# power.net
KiCad netlist of a schematic drawn in Altium Designer
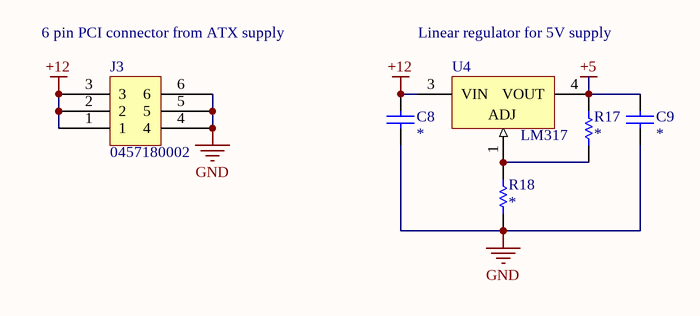
[diagram p0: power.SchDoc]

(export (version "E")
  (design (tool "Eeschema 10.0.6"))
  (components
    (comp (ref "C8")
      (value "*")
      (footprint "C0603")
      (description "0603 Capacitor")
      (fields (field (name "ALTIUM_VALUE") "*"))
      (libsource (lib "PARSEC") (part "C0603"))
    )
    (comp (ref "C9")
      (value "*")
      (footprint "C0805")
      (description "0805 Capacitor")
      (fields (field (name "ALTIUM_VALUE") "*"))
      (libsource (lib "PARSEC") (part "C0805"))
    )
    (comp (ref "J3") (value "0457180002") (libsource (lib "PARSEC") (part "0457180002")))
    (comp (ref "R17")
      (value "*")
      (footprint "R0603")
      (description "RESISTOR 0603")
      (fields (field (name "ALTIUM_VALUE") "*"))
      (libsource (lib "PARSEC") (part "R0603"))
    )
    (comp (ref "R18")
      (value "*")
      (footprint "R0603")
      (description "RESISTOR 0603")
      (fields (field (name "ALTIUM_VALUE") "*"))
      (libsource (lib "PARSEC") (part "R0603"))
    )
    (comp (ref "U4")
      (value "LM317")
      (footprint "D-PAK")
      (description "Linear Voltage Regulator")
      (libsource (lib "PARSEC") (part "LM317"))
    )
  )
  (nets
    (net (code "1") (name "+5") (class "Default")
      (node (ref "C9") (pin "1") (pinfunction "1_1") (pintype "passive"))
      (node (ref "R17") (pin "1") (pinfunction "1_1") (pintype "passive"))
      (node (ref "U4") (pin "4") (pinfunction "VOUT_4") (pintype "power_in"))
    )
    (net (code "2") (name "+12") (class "Default")
      (node (ref "C8") (pin "1") (pinfunction "1_1") (pintype "passive"))
      (node (ref "J3") (pin "1") (pinfunction "1_1") (pintype "passive"))
      (node (ref "J3") (pin "2") (pinfunction "2_2") (pintype "passive"))
      (node (ref "J3") (pin "3") (pinfunction "3_3") (pintype "passive"))
      (node (ref "U4") (pin "3") (pinfunction "VIN_3") (pintype "power_in"))
    )
    (net (code "3") (name "GND") (class "Default")
      (node (ref "C8") (pin "2") (pinfunction "2_2") (pintype "passive"))
      (node (ref "C9") (pin "2") (pinfunction "2_2") (pintype "passive"))
      (node (ref "J3") (pin "4") (pinfunction "4_4") (pintype "passive"))
      (node (ref "J3") (pin "5") (pinfunction "5_5") (pintype "passive"))
      (node (ref "J3") (pin "6") (pinfunction "6_6") (pintype "passive"))
      (node (ref "R18") (pin "2") (pinfunction "2_2") (pintype "passive"))
    )
    (net (code "4") (name "Net-(U4-ADJ)") (class "Default")
      (node (ref "R17") (pin "2") (pinfunction "2_2") (pintype "passive"))
      (node (ref "R18") (pin "1") (pinfunction "1_1") (pintype "passive"))
      (node (ref "U4") (pin "1") (pinfunction "ADJ_1") (pintype "input"))
    )
  )
)
